# 23D_ESC_Controller.net
KiCad netlist of a schematic drawn in Altium Designer
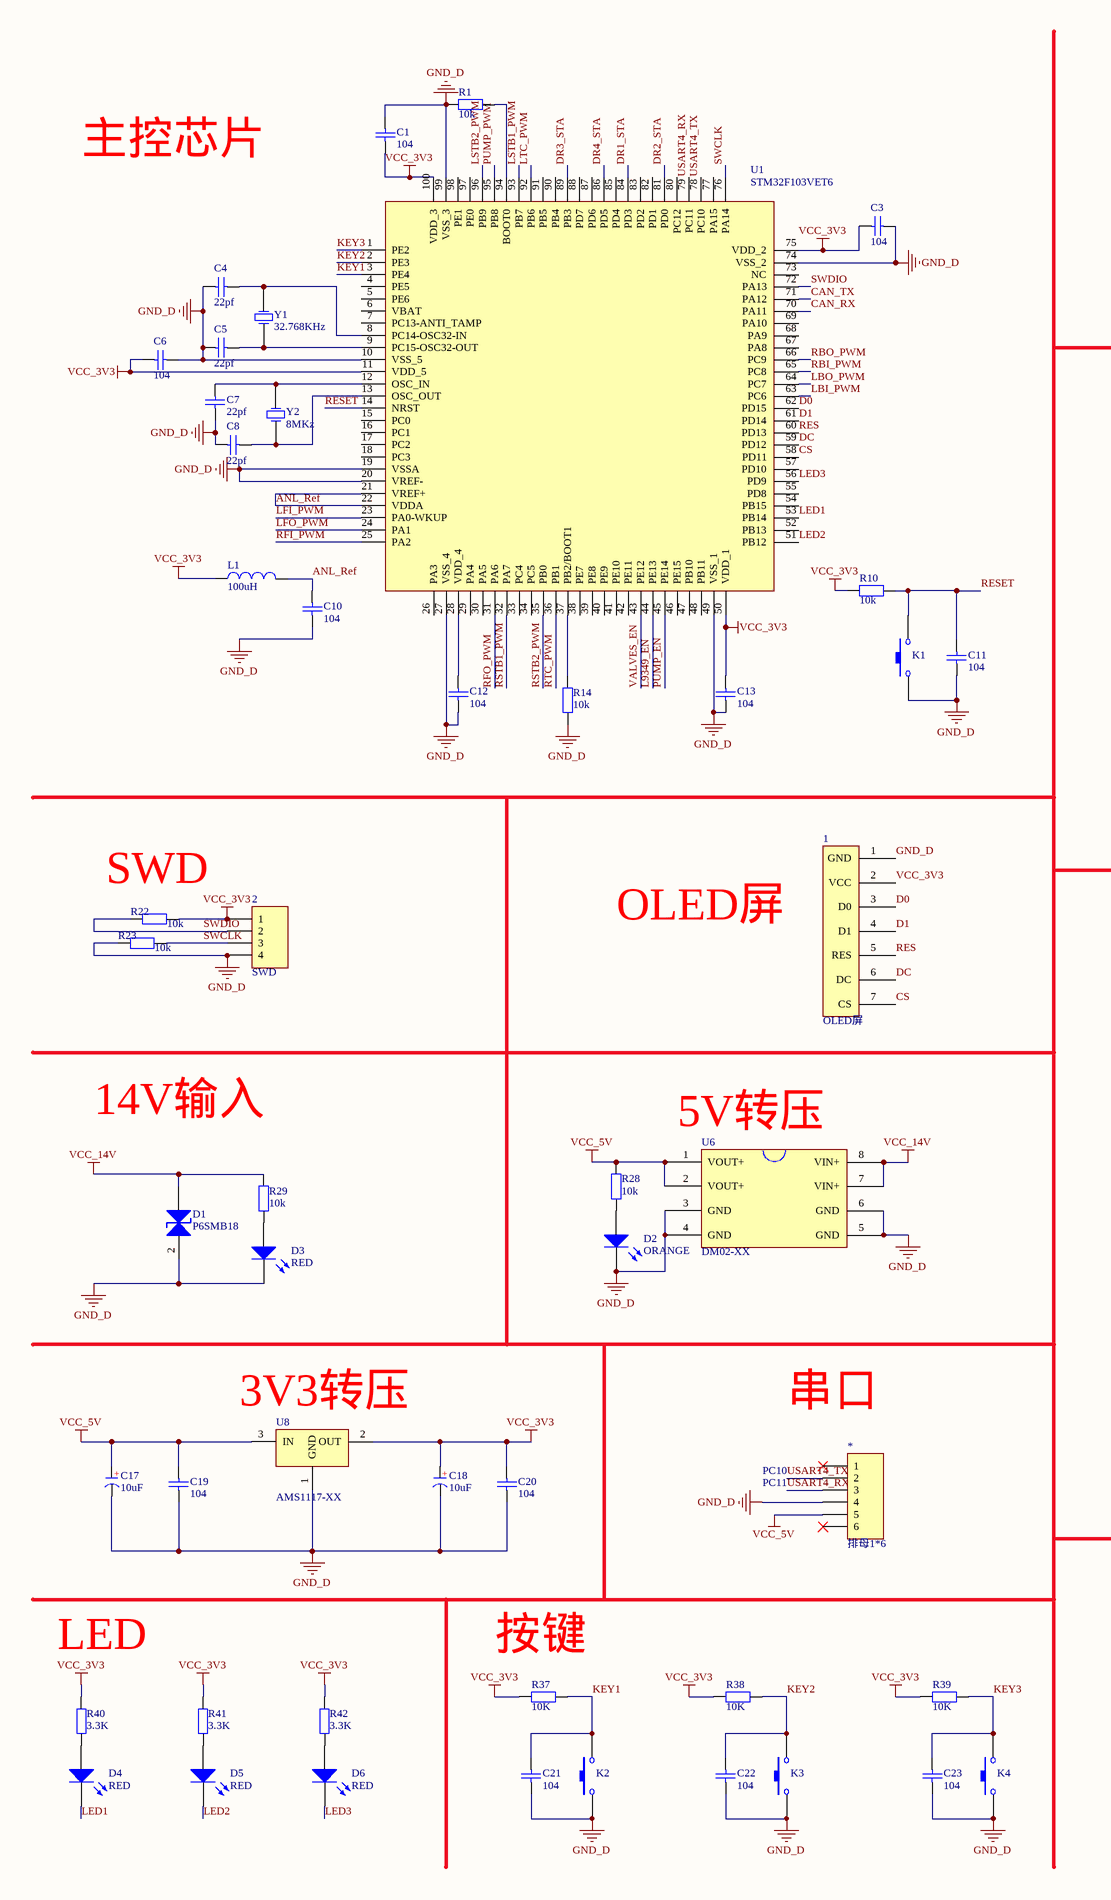
[diagram p0: 23D_ESC_Controller.SchDoc, left]
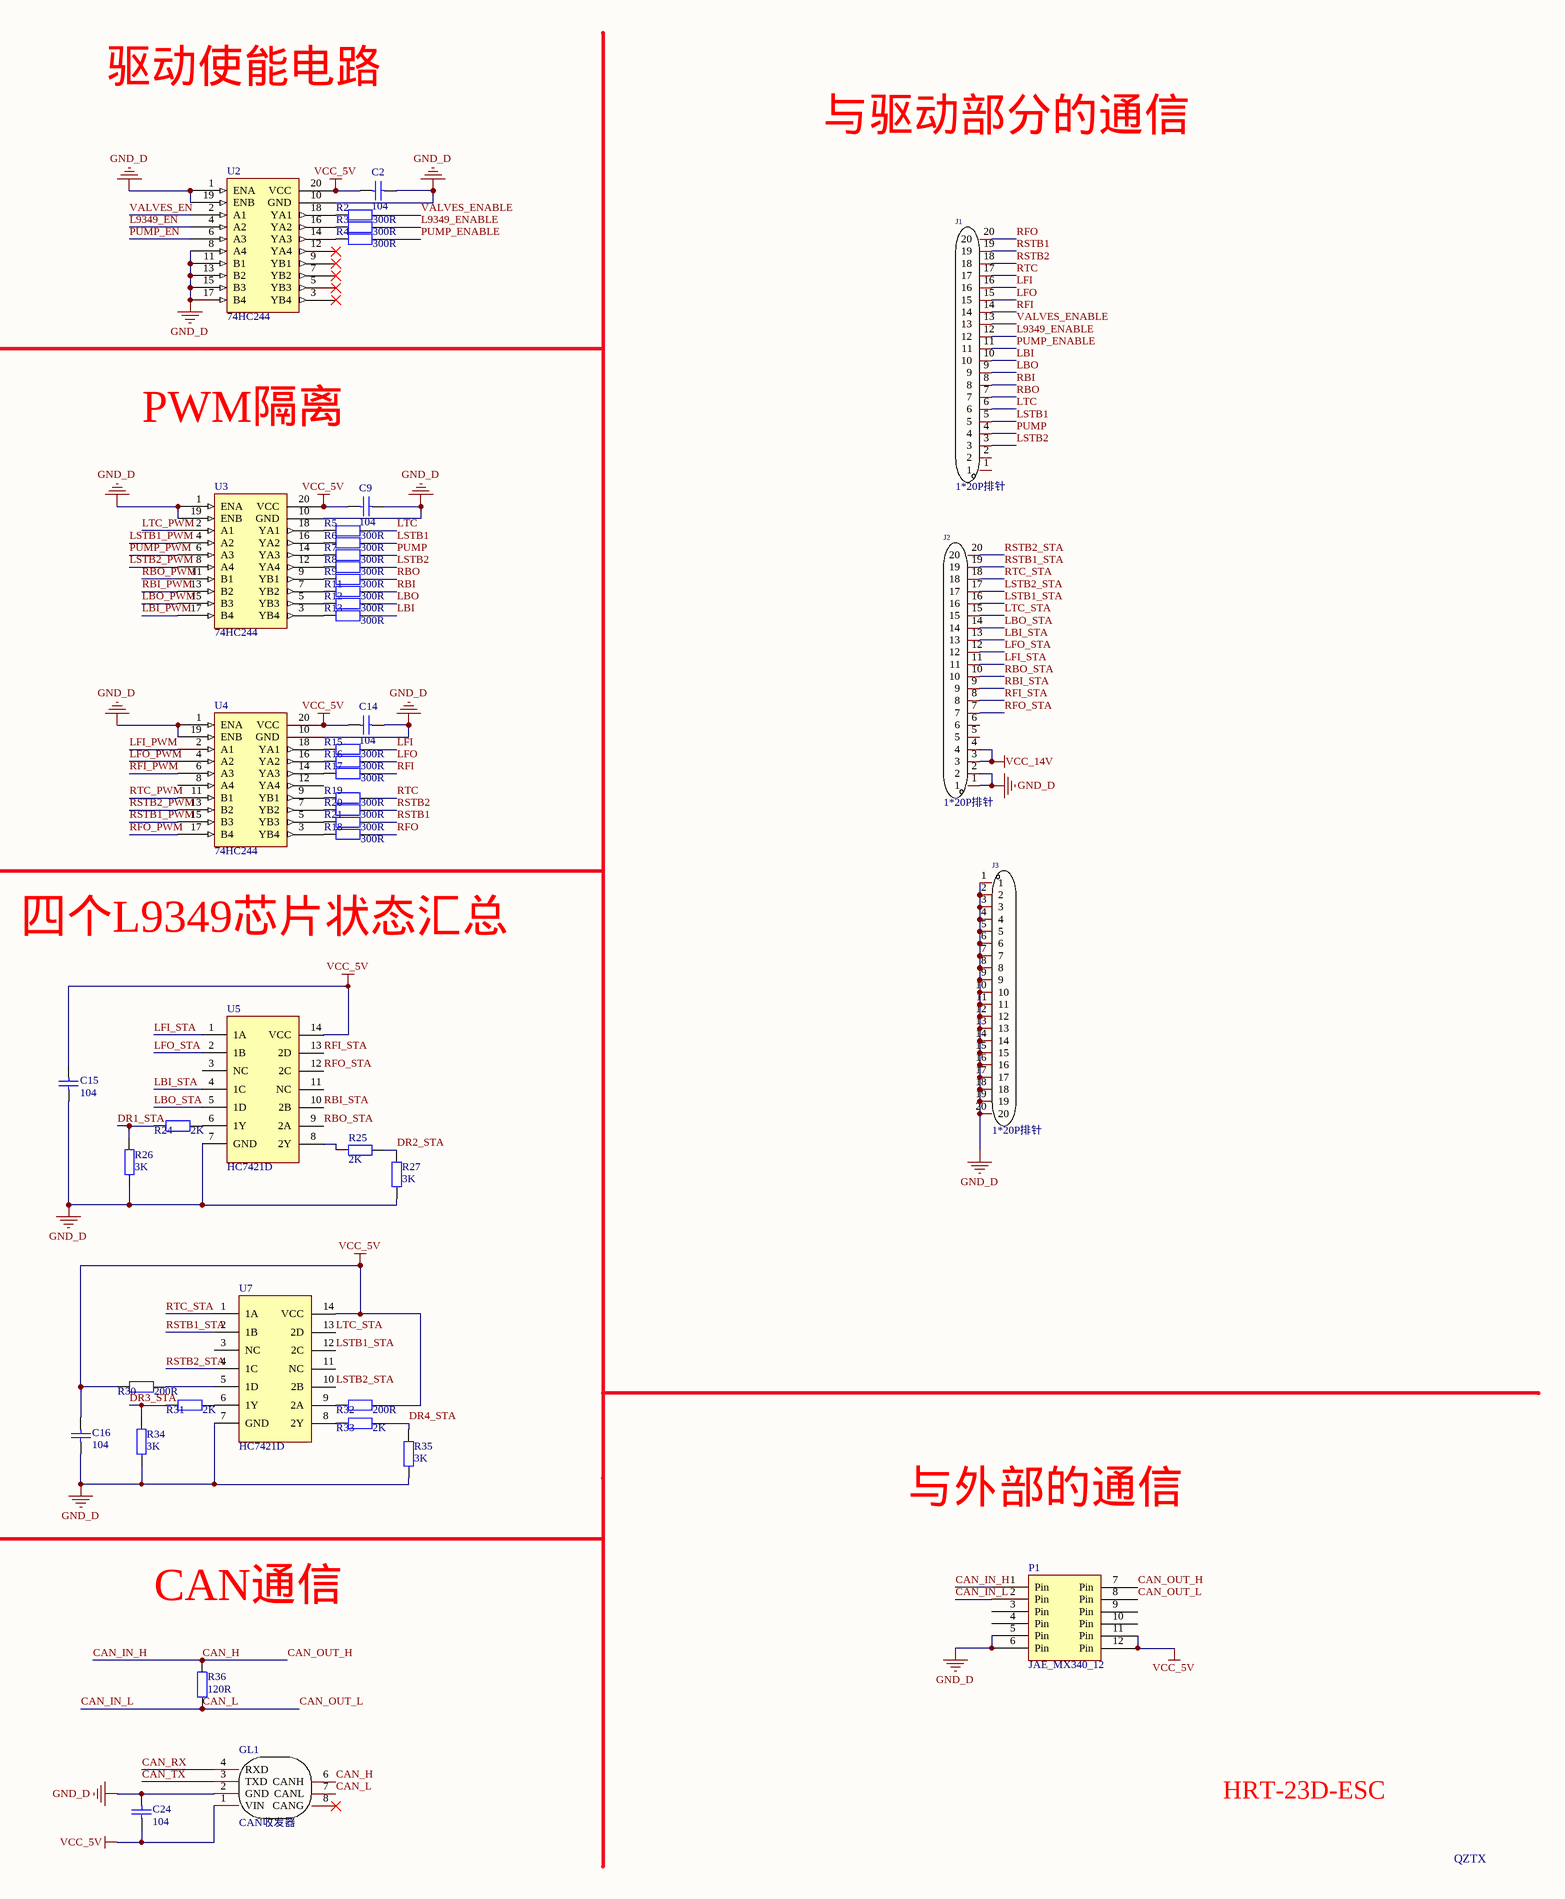
[diagram p1: 23D_ESC_Controller.SchDoc, right]

(export (version "E")
  (design (tool "Eeschema 10.0.6"))
  (components
    (comp (ref "*") (value "排母1*6") (footprint "HDR2.54-M-LI-6P") (libsource (lib "排针排母库") (part "排母1*6")))
    (comp (ref "1") (value "OLED屏") (footprint "HDR2.54-M-LI-7P") (libsource (lib "手柄按钮") (part "OLED屏")))
    (comp (ref "2") (value "SWD") (footprint "HDR2.54-LI-4P") (libsource (lib "排针排母库") (part "排针1*4")))
    (comp (ref "C1")
      (value "104")
      (footprint "C 0805")
      (description "无极性电容")
      (libsource (lib "HRT_D Schlib") (part "Cap"))
    )
    (comp (ref "C2")
      (value "104")
      (footprint "C 0805")
      (description "无极性电容")
      (libsource (lib "HRT_D Schlib") (part "Cap"))
    )
    (comp (ref "C3")
      (value "104")
      (footprint "C 0805")
      (description "无极性电容")
      (libsource (lib "HRT_D Schlib") (part "Cap"))
    )
    (comp (ref "C4")
      (value "22pf")
      (footprint "C 0805")
      (description "无极性电容")
      (libsource (lib "HRT_D Schlib") (part "Cap"))
    )
    (comp (ref "C5")
      (value "22pf")
      (footprint "C 0805")
      (description "无极性电容")
      (libsource (lib "HRT_D Schlib") (part "Cap"))
    )
    (comp (ref "C6")
      (value "104")
      (footprint "C 0805")
      (description "无极性电容")
      (libsource (lib "HRT_D Schlib") (part "Cap"))
    )
    (comp (ref "C7")
      (value "22pf")
      (footprint "C 0805")
      (description "无极性电容")
      (libsource (lib "HRT_D Schlib") (part "Cap"))
    )
    (comp (ref "C8")
      (value "22pf")
      (footprint "C 0805")
      (description "无极性电容")
      (libsource (lib "HRT_D Schlib") (part "Cap"))
    )
    (comp (ref "C9")
      (value "104")
      (footprint "C 0805")
      (description "无极性电容")
      (libsource (lib "HRT_D Schlib") (part "Cap"))
    )
    (comp (ref "C10")
      (value "104")
      (footprint "C 0805")
      (description "无极性电容")
      (libsource (lib "HRT_D Schlib") (part "Cap"))
    )
    (comp (ref "C11")
      (value "104")
      (footprint "C 0805")
      (description "无极性电容")
      (libsource (lib "HRT_D Schlib") (part "Cap"))
    )
    (comp (ref "C12")
      (value "104")
      (footprint "C 0805")
      (description "无极性电容")
      (libsource (lib "HRT_D Schlib") (part "Cap"))
    )
    (comp (ref "C13")
      (value "104")
      (footprint "C 0805")
      (description "无极性电容")
      (libsource (lib "HRT_D Schlib") (part "Cap"))
    )
    (comp (ref "C14")
      (value "104")
      (footprint "C 0805")
      (description "无极性电容")
      (libsource (lib "HRT_D Schlib") (part "Cap"))
    )
    (comp (ref "C15")
      (value "104")
      (footprint "C 0805")
      (description "无极性电容")
      (libsource (lib "HRT_D Schlib") (part "Cap"))
    )
    (comp (ref "C16")
      (value "104")
      (footprint "C 0805")
      (description "无极性电容")
      (libsource (lib "HRT_D Schlib") (part "Cap"))
    )
    (comp (ref "C17")
      (value "10uF")
      (footprint "CD B(3528)")
      (libsource (lib "USB_Gamepad_board") (part "贴片钽电容"))
    )
    (comp (ref "C18")
      (value "10uF")
      (footprint "CD B(3528)")
      (libsource (lib "USB_Gamepad_board") (part "贴片钽电容"))
    )
    (comp (ref "C19")
      (value "104")
      (footprint "C 0805")
      (description "无极性电容")
      (libsource (lib "HRT_D Schlib") (part "Cap"))
    )
    (comp (ref "C20")
      (value "104")
      (footprint "C 0805")
      (description "无极性电容")
      (libsource (lib "HRT_D Schlib") (part "Cap"))
    )
    (comp (ref "C21")
      (value "104")
      (footprint "C 0805")
      (description "无极性电容")
      (libsource (lib "HRT_D Schlib") (part "Cap"))
    )
    (comp (ref "C22")
      (value "104")
      (footprint "C 0805")
      (description "无极性电容")
      (libsource (lib "HRT_D Schlib") (part "Cap"))
    )
    (comp (ref "C23")
      (value "104")
      (footprint "C 0805")
      (description "无极性电容")
      (libsource (lib "HRT_D Schlib") (part "Cap"))
    )
    (comp (ref "C24")
      (value "104")
      (footprint "C 0805")
      (description "无极性电容")
      (libsource (lib "HRT_D Schlib") (part "Cap"))
    )
    (comp (ref "D1")
      (value "P6SMB18")
      (footprint "DO-214AA")
      (description "BiDir TVS Diode")
      (libsource (lib "ER100_ESC") (part "P6SMBXX"))
    )
    (comp (ref "D2")
      (value "ORANGE")
      (footprint "LED_0805")
      (description "发光二极管")
      (libsource (lib "ESC_control") (part "LED"))
    )
    (comp (ref "D3")
      (value "RED")
      (footprint "LED_0805")
      (description "发光二极管")
      (libsource (lib "ESC_control") (part "LED"))
    )
    (comp (ref "D4")
      (value "RED")
      (footprint "LED_0805")
      (description "发光二极管")
      (libsource (lib "ESC_control") (part "LED"))
    )
    (comp (ref "D5")
      (value "RED")
      (footprint "LED_0805")
      (description "发光二极管")
      (libsource (lib "ESC_control") (part "LED"))
    )
    (comp (ref "D6")
      (value "RED")
      (footprint "LED_0805")
      (description "发光二极管")
      (libsource (lib "ESC_control") (part "LED"))
    )
    (comp (ref "GL1")
      (value "CTM1051KT")
      (footprint "COMM-TH_7P-L19.9-W17.5-P2.54")
      (description "兼容3.3V和5V的单片机CAN接口，CAN隔离收发器 5V供电")
      (fields (field (name "MANUFACTURER") "ZLG(致远电子)") (field (name "NAME") "CAN收发器"))
      (libsource (lib "CTM1051KT大方块") (part "CTM1051KT_C84516"))
    )
    (comp (ref "J1")
      (value "2.54-1*20P直针")
      (footprint "HDR-TH_20P-P2.54-V-M-1")
      (fields (field (name "MANUFACTURER") "BOOMELE(博穆精密)") (field (name "NAME") "1*20P排针"))
      (libsource (lib "20P排针2.54mm") (part "2.54-1*20P直针"))
    )
    (comp (ref "J2")
      (value "2.54-1*20P直针")
      (footprint "HDR-TH_20P-P2.54-V-M-1")
      (fields (field (name "MANUFACTURER") "BOOMELE(博穆精密)") (field (name "NAME") "1*20P排针"))
      (libsource (lib "20P排针2.54mm") (part "2.54-1*20P直针"))
    )
    (comp (ref "J3")
      (value "2.54-1*20P直针")
      (footprint "HDR2.54-LI-20P")
      (fields (field (name "MANUFACTURER") "BOOMELE(博穆精密)") (field (name "NAME") "1*20P排针"))
      (libsource (lib "20P排针2.54mm") (part "2.54-1*20P直针"))
    )
    (comp (ref "K1")
      (value "Key")
      (footprint "KEY 3.6*2.5 SMD")
      (description "按键")
      (libsource (lib "HRT_D Schlib") (part "Key"))
    )
    (comp (ref "K2")
      (value "Key")
      (footprint "KEY 3.6*2.5 SMD")
      (description "按键")
      (libsource (lib "HRT_D Schlib") (part "Key"))
    )
    (comp (ref "K3")
      (value "Key")
      (footprint "KEY 3.6*2.5 SMD")
      (description "按键")
      (libsource (lib "HRT_D Schlib") (part "Key"))
    )
    (comp (ref "K4")
      (value "Key")
      (footprint "KEY 3.6*2.5 SMD")
      (description "按键")
      (libsource (lib "HRT_D Schlib") (part "Key"))
    )
    (comp (ref "L1")
      (value "100uH")
      (footprint "L 0805")
      (description "电感")
      (libsource (lib "ESC_control") (part "Inductor"))
    )
    (comp (ref "P1")
      (value "JAE_MX340_12")
      (footprint "JAE_MX34_2.2_12")
      (libsource (lib "ESC_control") (part "JAE_MX34012NF1"))
    )
    (comp (ref "R1")
      (value "10k")
      (footprint "R 0805")
      (description "电阻")
      (libsource (lib "ESC_control") (part "Resistor"))
    )
    (comp (ref "R2")
      (value "300R")
      (footprint "R 0805")
      (description "电阻")
      (libsource (lib "") (part "Resistor_1"))
    )
    (comp (ref "R3")
      (value "300R")
      (footprint "R 0805")
      (description "电阻")
      (libsource (lib "") (part "Resistor_1"))
    )
    (comp (ref "R4")
      (value "300R")
      (footprint "R 0805")
      (description "电阻")
      (libsource (lib "") (part "Resistor_1"))
    )
    (comp (ref "R5")
      (value "300R")
      (footprint "R 0805")
      (description "电阻")
      (libsource (lib "") (part "Resistor_1"))
    )
    (comp (ref "R6")
      (value "300R")
      (footprint "R 0805")
      (description "电阻")
      (libsource (lib "") (part "Resistor_1"))
    )
    (comp (ref "R7")
      (value "300R")
      (footprint "R 0805")
      (description "电阻")
      (libsource (lib "") (part "Resistor_1"))
    )
    (comp (ref "R8")
      (value "300R")
      (footprint "R 0805")
      (description "电阻")
      (libsource (lib "") (part "Resistor_1"))
    )
    (comp (ref "R9")
      (value "300R")
      (footprint "R 0805")
      (description "电阻")
      (libsource (lib "") (part "Resistor_1"))
    )
    (comp (ref "R10")
      (value "10k")
      (footprint "R 0805")
      (description "电阻")
      (libsource (lib "") (part "Resistor_1"))
    )
    (comp (ref "R11")
      (value "300R")
      (footprint "R 0805")
      (description "电阻")
      (libsource (lib "") (part "Resistor_1"))
    )
    (comp (ref "R12")
      (value "300R")
      (footprint "R 0805")
      (description "电阻")
      (libsource (lib "") (part "Resistor_1"))
    )
    (comp (ref "R13")
      (value "300R")
      (footprint "R 0805")
      (description "电阻")
      (libsource (lib "") (part "Resistor_1"))
    )
    (comp (ref "R14")
      (value "10k")
      (footprint "R 0805")
      (description "电阻")
      (libsource (lib "") (part "Resistor_3"))
    )
    (comp (ref "R15")
      (value "300R")
      (footprint "R 0805")
      (description "电阻")
      (libsource (lib "") (part "Resistor_1"))
    )
    (comp (ref "R16")
      (value "300R")
      (footprint "R 0805")
      (description "电阻")
      (libsource (lib "") (part "Resistor_1"))
    )
    (comp (ref "R17")
      (value "300R")
      (footprint "R 0805")
      (description "电阻")
      (libsource (lib "") (part "Resistor_1"))
    )
    (comp (ref "R18")
      (value "300R")
      (footprint "R 0805")
      (description "电阻")
      (libsource (lib "") (part "Resistor_1"))
    )
    (comp (ref "R19")
      (value "300R")
      (footprint "R 0805")
      (description "电阻")
      (libsource (lib "") (part "Resistor_1"))
    )
    (comp (ref "R20")
      (value "300R")
      (footprint "R 0805")
      (description "电阻")
      (libsource (lib "") (part "Resistor_1"))
    )
    (comp (ref "R21")
      (value "300R")
      (footprint "R 0805")
      (description "电阻")
      (libsource (lib "") (part "Resistor_1"))
    )
    (comp (ref "R22")
      (value "10k")
      (footprint "R 0805")
      (description "电阻")
      (libsource (lib "") (part "Resistor_1"))
    )
    (comp (ref "R23")
      (value "10k")
      (footprint "R 0805")
      (description "电阻")
      (libsource (lib "") (part "Resistor_1"))
    )
    (comp (ref "R24")
      (value "2K")
      (footprint "R 0805")
      (description "电阻")
      (libsource (lib "ESC_control") (part "Resistor"))
    )
    (comp (ref "R25")
      (value "2K")
      (footprint "R 0805")
      (description "电阻")
      (libsource (lib "") (part "Resistor_1"))
    )
    (comp (ref "R26")
      (value "3K")
      (footprint "R 0805")
      (description "电阻")
      (libsource (lib "") (part "Resistor_2"))
    )
    (comp (ref "R27")
      (value "3K")
      (footprint "R 0805")
      (description "电阻")
      (libsource (lib "") (part "Resistor_3"))
    )
    (comp (ref "R28")
      (value "10k")
      (footprint "R 0805")
      (description "电阻")
      (libsource (lib "") (part "Resistor_2"))
    )
    (comp (ref "R29")
      (value "10k")
      (footprint "R 0805")
      (description "电阻")
      (libsource (lib "") (part "Resistor_2"))
    )
    (comp (ref "R30")
      (value "200R")
      (footprint "R 0805")
      (description "电阻")
      (libsource (lib "ESC_control") (part "Resistor"))
    )
    (comp (ref "R31")
      (value "2K")
      (footprint "R 0805")
      (description "电阻")
      (libsource (lib "ESC_control") (part "Resistor"))
    )
    (comp (ref "R32")
      (value "200R")
      (footprint "R 0805")
      (description "电阻")
      (libsource (lib "ESC_control") (part "Resistor"))
    )
    (comp (ref "R33")
      (value "2K")
      (footprint "R 0805")
      (description "电阻")
      (libsource (lib "ESC_control") (part "Resistor"))
    )
    (comp (ref "R34")
      (value "3K")
      (footprint "R 0805")
      (description "电阻")
      (libsource (lib "") (part "Resistor_2"))
    )
    (comp (ref "R35")
      (value "3K")
      (footprint "R 0805")
      (description "电阻")
      (libsource (lib "") (part "Resistor_3"))
    )
    (comp (ref "R36")
      (value "120R")
      (footprint "R 0805")
      (description "电阻")
      (libsource (lib "") (part "Resistor_3"))
    )
    (comp (ref "R37")
      (value "10K")
      (footprint "R 0805")
      (description "电阻")
      (libsource (lib "ESC_control") (part "Resistor"))
    )
    (comp (ref "R38")
      (value "10K")
      (footprint "R 0805")
      (description "电阻")
      (libsource (lib "ESC_control") (part "Resistor"))
    )
    (comp (ref "R39")
      (value "10K")
      (footprint "R 0805")
      (description "电阻")
      (libsource (lib "ESC_control") (part "Resistor"))
    )
    (comp (ref "R40")
      (value "3.3K")
      (footprint "R 0805")
      (description "电阻")
      (libsource (lib "") (part "Resistor_2"))
    )
    (comp (ref "R41")
      (value "3.3K")
      (footprint "R 0805")
      (description "电阻")
      (libsource (lib "") (part "Resistor_2"))
    )
    (comp (ref "R42")
      (value "3.3K")
      (footprint "R 0805")
      (description "电阻")
      (libsource (lib "") (part "Resistor_2"))
    )
    (comp (ref "U1")
      (value "STM32F103VET6")
      (footprint "TQFP100N50P14X14X1.2")
      (libsource (lib "STM32") (part "STM32F103RBT6"))
    )
    (comp (ref "U2")
      (value "74HC244")
      (footprint "SSOP20")
      (description "CMOS工艺8通道缓冲器")
      (libsource (lib "ESC_control") (part "74HC244"))
    )
    (comp (ref "U3")
      (value "74HC244")
      (footprint "SSOP20")
      (description "CMOS工艺8通道缓冲器")
      (libsource (lib "ESC_control") (part "74HC244"))
    )
    (comp (ref "U4")
      (value "74HC244")
      (footprint "SSOP20")
      (description "CMOS工艺8通道缓冲器")
      (libsource (lib "ESC_control") (part "74HC244"))
    )
    (comp (ref "U5") (value "HC7421D") (footprint "74hc74") (libsource (lib "ESC_control") (part "HC7421D")))
    (comp (ref "U6")
      (value "DM02-XX")
      (footprint "DM02")
      (description "开关型DC-DC变换器")
      (libsource (lib "ESC_control") (part "DM02"))
    )
    (comp (ref "U7") (value "HC7421D") (footprint "74hc74") (libsource (lib "ESC_control") (part "HC7421D")))
    (comp (ref "U8")
      (value "AMS1117-XX")
      (footprint "SOT223")
      (description "线性稳压器")
      (libsource (lib "HRT_D Schlib") (part "AMS1117"))
    )
    (comp (ref "Y1")
      (value "32.768KHz")
      (footprint "XTAL-5032")
      (description "晶振")
      (libsource (lib "ESC_control") (part "XTAL"))
    )
    (comp (ref "Y2")
      (value "8MKz")
      (footprint "XTAL-5032")
      (description "晶振")
      (libsource (lib "ESC_control") (part "XTAL"))
    )
  )
  (nets
    (net (code "1") (name "/ANL_Ref") (class "Default")
      (node (ref "C10") (pin "1") (pinfunction "1_1") (pintype "passive"))
      (node (ref "L1") (pin "2") (pinfunction "2_2") (pintype "passive"))
      (node (ref "U1") (pin "21") (pinfunction "VREF+_21") (pintype "passive"))
      (node (ref "U1") (pin "22") (pinfunction "VDDA_22") (pintype "passive"))
    )
    (net (code "2") (name "/CAN_H") (class "Default")
      (node (ref "GL1") (pin "6") (pinfunction "CANH_6") (pintype "passive"))
      (node (ref "P1") (pin "1") (pinfunction "Pin_1") (pintype "passive"))
      (node (ref "P1") (pin "7") (pinfunction "Pin_7") (pintype "passive"))
      (node (ref "R36") (pin "1") (pinfunction "1_1") (pintype "passive"))
    )
    (net (code "3") (name "/CAN_IN_L") (class "Default")
      (node (ref "GL1") (pin "7") (pinfunction "CANL_7") (pintype "passive"))
      (node (ref "P1") (pin "2") (pinfunction "Pin_2") (pintype "passive"))
      (node (ref "P1") (pin "8") (pinfunction "Pin_8") (pintype "passive"))
      (node (ref "R36") (pin "2") (pinfunction "2_2") (pintype "passive"))
    )
    (net (code "4") (name "/CAN_RX") (class "Default")
      (node (ref "GL1") (pin "4") (pinfunction "RXD_4") (pintype "passive"))
      (node (ref "U1") (pin "70") (pinfunction "PA11_70") (pintype "passive"))
    )
    (net (code "5") (name "/CAN_TX") (class "Default")
      (node (ref "GL1") (pin "3") (pinfunction "TXD_3") (pintype "passive"))
      (node (ref "U1") (pin "71") (pinfunction "PA12_71") (pintype "passive"))
    )
    (net (code "6") (name "/CS") (class "Default")
      (node (ref "1") (pin "7") (pinfunction "CS_7") (pintype "passive"))
      (node (ref "U1") (pin "58") (pinfunction "PD11_58") (pintype "passive"))
    )
    (net (code "7") (name "/D0") (class "Default")
      (node (ref "1") (pin "3") (pinfunction "D0_3") (pintype "passive"))
      (node (ref "U1") (pin "62") (pinfunction "PD15_62") (pintype "passive"))
    )
    (net (code "8") (name "/D1") (class "Default")
      (node (ref "1") (pin "4") (pinfunction "D1_4") (pintype "passive"))
      (node (ref "U1") (pin "61") (pinfunction "PD14_61") (pintype "passive"))
    )
    (net (code "9") (name "/DC") (class "Default")
      (node (ref "1") (pin "6") (pinfunction "DC_6") (pintype "passive"))
      (node (ref "U1") (pin "59") (pinfunction "PD12_59") (pintype "passive"))
    )
    (net (code "10") (name "/DR1_STA") (class "Default")
      (node (ref "R24") (pin "2") (pinfunction "2_2") (pintype "passive"))
      (node (ref "R26") (pin "2") (pinfunction "2_2") (pintype "passive"))
      (node (ref "U1") (pin "84") (pinfunction "PD3_84") (pintype "passive"))
    )
    (net (code "11") (name "/DR2_STA") (class "Default")
      (node (ref "R25") (pin "2") (pinfunction "2_2") (pintype "passive"))
      (node (ref "R27") (pin "1") (pinfunction "1_1") (pintype "passive"))
      (node (ref "U1") (pin "81") (pinfunction "PD0_81") (pintype "passive"))
    )
    (net (code "12") (name "/DR3_STA") (class "Default")
      (node (ref "R31") (pin "2") (pinfunction "2_2") (pintype "passive"))
      (node (ref "R34") (pin "2") (pinfunction "2_2") (pintype "passive"))
      (node (ref "U1") (pin "89") (pinfunction "PB3_89") (pintype "passive"))
    )
    (net (code "13") (name "/DR4_STA") (class "Default")
      (node (ref "R33") (pin "1") (pinfunction "1_1") (pintype "passive"))
      (node (ref "R35") (pin "1") (pinfunction "1_1") (pintype "passive"))
      (node (ref "U1") (pin "86") (pinfunction "PD5_86") (pintype "passive"))
    )
    (net (code "14") (name "/KEY1") (class "Default")
      (node (ref "C21") (pin "1") (pinfunction "1_1") (pintype "passive"))
      (node (ref "K2") (pin "2") (pinfunction "2_2") (pintype "passive"))
      (node (ref "R37") (pin "1") (pinfunction "1_1") (pintype "passive"))
      (node (ref "U1") (pin "3") (pinfunction "PE4_3") (pintype "passive"))
    )
    (net (code "15") (name "/KEY2") (class "Default")
      (node (ref "C22") (pin "1") (pinfunction "1_1") (pintype "passive"))
      (node (ref "K3") (pin "2") (pinfunction "2_2") (pintype "passive"))
      (node (ref "R38") (pin "1") (pinfunction "1_1") (pintype "passive"))
      (node (ref "U1") (pin "2") (pinfunction "PE3_2") (pintype "passive"))
    )
    (net (code "16") (name "/KEY3") (class "Default")
      (node (ref "C23") (pin "1") (pinfunction "1_1") (pintype "passive"))
      (node (ref "K4") (pin "2") (pinfunction "2_2") (pintype "passive"))
      (node (ref "R39") (pin "1") (pinfunction "1_1") (pintype "passive"))
      (node (ref "U1") (pin "1") (pinfunction "PE2_1") (pintype "passive"))
    )
    (net (code "17") (name "/L9349_EN") (class "Default")
      (node (ref "U1") (pin "44") (pinfunction "PE13_44") (pintype "passive"))
      (node (ref "U2") (pin "4") (pinfunction "A2_4") (pintype "input"))
    )
    (net (code "18") (name "/L9349_ENABLE") (class "Default")
      (node (ref "J1") (pin "12") (pinfunction "12_12") (pintype "passive"))
      (node (ref "R3") (pin "2") (pinfunction "2_2") (pintype "passive"))
    )
    (net (code "19") (name "/LBI") (class "Default")
      (node (ref "J1") (pin "10") (pinfunction "10_10") (pintype "passive"))
      (node (ref "R13") (pin "2") (pinfunction "2_2") (pintype "passive"))
    )
    (net (code "20") (name "/LBI_PWM") (class "Default")
      (node (ref "U1") (pin "63") (pinfunction "PC6_63") (pintype "passive"))
      (node (ref "U3") (pin "17") (pinfunction "B4_17") (pintype "input"))
    )
    (net (code "21") (name "/LBI_STA") (class "Default")
      (node (ref "J2") (pin "13") (pinfunction "13_13") (pintype "passive"))
      (node (ref "U5") (pin "4") (pinfunction "1C_4") (pintype "passive"))
    )
    (net (code "22") (name "/LBO") (class "Default")
      (node (ref "J1") (pin "9") (pinfunction "9_9") (pintype "passive"))
      (node (ref "R12") (pin "2") (pinfunction "2_2") (pintype "passive"))
    )
    (net (code "23") (name "/LBO_PWM") (class "Default")
      (node (ref "U1") (pin "64") (pinfunction "PC7_64") (pintype "passive"))
      (node (ref "U3") (pin "15") (pinfunction "B3_15") (pintype "input"))
    )
    (net (code "24") (name "/LBO_STA") (class "Default")
      (node (ref "J2") (pin "14") (pinfunction "14_14") (pintype "passive"))
      (node (ref "U5") (pin "5") (pinfunction "1D_5") (pintype "passive"))
    )
    (net (code "25") (name "/LED1") (class "Default")
      (node (ref "D4") (pin "2") (pinfunction "K_2") (pintype "passive"))
      (node (ref "U1") (pin "53") (pinfunction "PB14_53") (pintype "passive"))
    )
    (net (code "26") (name "/LED2") (class "Default")
      (node (ref "D5") (pin "2") (pinfunction "K_2") (pintype "passive"))
      (node (ref "U1") (pin "51") (pinfunction "PB12_51") (pintype "passive"))
    )
    (net (code "27") (name "/LED3") (class "Default")
      (node (ref "D6") (pin "2") (pinfunction "K_2") (pintype "passive"))
      (node (ref "U1") (pin "56") (pinfunction "PD9_56") (pintype "passive"))
    )
    (net (code "28") (name "/LFI") (class "Default")
      (node (ref "J1") (pin "16") (pinfunction "16_16") (pintype "passive"))
      (node (ref "R15") (pin "2") (pinfunction "2_2") (pintype "passive"))
    )
    (net (code "29") (name "/LFI_PWM") (class "Default")
      (node (ref "U1") (pin "23") (pinfunction "PA0-WKUP_23") (pintype "passive"))
      (node (ref "U4") (pin "2") (pinfunction "A1_2") (pintype "input"))
    )
    (net (code "30") (name "/LFI_STA") (class "Default")
      (node (ref "J2") (pin "11") (pinfunction "11_11") (pintype "passive"))
      (node (ref "U5") (pin "1") (pinfunction "1A_1") (pintype "passive"))
    )
    (net (code "31") (name "/LFO") (class "Default")
      (node (ref "J1") (pin "15") (pinfunction "15_15") (pintype "passive"))
      (node (ref "R16") (pin "2") (pinfunction "2_2") (pintype "passive"))
    )
    (net (code "32") (name "/LFO_PWM") (class "Default")
      (node (ref "U1") (pin "24") (pinfunction "PA1_24") (pintype "passive"))
      (node (ref "U4") (pin "4") (pinfunction "A2_4") (pintype "input"))
    )
    (net (code "33") (name "/LFO_STA") (class "Default")
      (node (ref "J2") (pin "12") (pinfunction "12_12") (pintype "passive"))
      (node (ref "U5") (pin "2") (pinfunction "1B_2") (pintype "passive"))
    )
    (net (code "34") (name "/LSTB1") (class "Default")
      (node (ref "J1") (pin "5") (pinfunction "5_5") (pintype "passive"))
      (node (ref "R6") (pin "2") (pinfunction "2_2") (pintype "passive"))
    )
    (net (code "35") (name "/LSTB1_PWM") (class "Default")
      (node (ref "U1") (pin "93") (pinfunction "PB7_93") (pintype "passive"))
      (node (ref "U3") (pin "4") (pinfunction "A2_4") (pintype "input"))
    )
    (net (code "36") (name "/LSTB1_STA") (class "Default")
      (node (ref "J2") (pin "16") (pinfunction "16_16") (pintype "passive"))
      (node (ref "U7") (pin "12") (pinfunction "2C_12") (pintype "passive"))
    )
    (net (code "37") (name "/LSTB2") (class "Default")
      (node (ref "J1") (pin "3") (pinfunction "3_3") (pintype "passive"))
      (node (ref "R8") (pin "2") (pinfunction "2_2") (pintype "passive"))
    )
    (net (code "38") (name "/LSTB2_PWM") (class "Default")
      (node (ref "U1") (pin "96") (pinfunction "PB9_96") (pintype "passive"))
      (node (ref "U3") (pin "8") (pinfunction "A4_8") (pintype "input"))
    )
    (net (code "39") (name "/LSTB2_STA") (class "Default")
      (node (ref "J2") (pin "17") (pinfunction "17_17") (pintype "passive"))
      (node (ref "U7") (pin "10") (pinfunction "2B_10") (pintype "passive"))
    )
    (net (code "40") (name "/LTC") (class "Default")
      (node (ref "J1") (pin "6") (pinfunction "6_6") (pintype "passive"))
      (node (ref "R5") (pin "2") (pinfunction "2_2") (pintype "passive"))
    )
    (net (code "41") (name "/LTC_PWM") (class "Default")
      (node (ref "U1") (pin "92") (pinfunction "PB6_92") (pintype "passive"))
      (node (ref "U3") (pin "2") (pinfunction "A1_2") (pintype "input"))
    )
    (net (code "42") (name "/LTC_STA") (class "Default")
      (node (ref "J2") (pin "15") (pinfunction "15_15") (pintype "passive"))
      (node (ref "U7") (pin "13") (pinfunction "2D_13") (pintype "passive"))
    )
    (net (code "43") (name "/PUMP") (class "Default")
      (node (ref "J1") (pin "4") (pinfunction "4_4") (pintype "passive"))
      (node (ref "R7") (pin "2") (pinfunction "2_2") (pintype "passive"))
    )
    (net (code "44") (name "/PUMP_EN") (class "Default")
      (node (ref "U1") (pin "45") (pinfunction "PE14_45") (pintype "passive"))
      (node (ref "U2") (pin "6") (pinfunction "A3_6") (pintype "input"))
    )
    (net (code "45") (name "/PUMP_ENABLE") (class "Default")
      (node (ref "J1") (pin "11") (pinfunction "11_11") (pintype "passive"))
      (node (ref "R4") (pin "2") (pinfunction "2_2") (pintype "passive"))
    )
    (net (code "46") (name "/PUMP_PWM") (class "Default")
      (node (ref "U1") (pin "95") (pinfunction "PB8_95") (pintype "passive"))
      (node (ref "U3") (pin "6") (pinfunction "A3_6") (pintype "input"))
    )
    (net (code "47") (name "/RBI") (class "Default")
      (node (ref "J1") (pin "8") (pinfunction "8_8") (pintype "passive"))
      (node (ref "R11") (pin "2") (pinfunction "2_2") (pintype "passive"))
    )
    (net (code "48") (name "/RBI_PWM") (class "Default")
      (node (ref "U1") (pin "65") (pinfunction "PC8_65") (pintype "passive"))
      (node (ref "U3") (pin "13") (pinfunction "B2_13") (pintype "input"))
    )
    (net (code "49") (name "/RBI_STA") (class "Default")
      (node (ref "J2") (pin "9") (pinfunction "9_9") (pintype "passive"))
      (node (ref "U5") (pin "10") (pinfunction "2B_10") (pintype "passive"))
    )
    (net (code "50") (name "/RBO") (class "Default")
      (node (ref "J1") (pin "7") (pinfunction "7_7") (pintype "passive"))
      (node (ref "R9") (pin "2") (pinfunction "2_2") (pintype "passive"))
    )
    (net (code "51") (name "/RBO_PWM") (class "Default")
      (node (ref "U1") (pin "66") (pinfunction "PC9_66") (pintype "passive"))
      (node (ref "U3") (pin "11") (pinfunction "B1_11") (pintype "input"))
    )
    (net (code "52") (name "/RBO_STA") (class "Default")
      (node (ref "J2") (pin "10") (pinfunction "10_10") (pintype "passive"))
      (node (ref "U5") (pin "9") (pinfunction "2A_9") (pintype "passive"))
    )
    (net (code "53") (name "/RES") (class "Default")
      (node (ref "1") (pin "5") (pinfunction "RES_5") (pintype "passive"))
      (node (ref "U1") (pin "60") (pinfunction "PD13_60") (pintype "passive"))
    )
    (net (code "54") (name "/RESET") (class "Default")
      (node (ref "C11") (pin "1") (pinfunction "1_1") (pintype "passive"))
      (node (ref "K1") (pin "2") (pinfunction "2_2") (pintype "passive"))
      (node (ref "R10") (pin "2") (pinfunction "2_2") (pintype "passive"))
      (node (ref "U1") (pin "14") (pinfunction "NRST_14") (pintype "passive"))
    )
    (net (code "55") (name "/RFI") (class "Default")
      (node (ref "J1") (pin "14") (pinfunction "14_14") (pintype "passive"))
      (node (ref "R17") (pin "2") (pinfunction "2_2") (pintype "passive"))
    )
    (net (code "56") (name "/RFI_PWM") (class "Default")
      (node (ref "U1") (pin "25") (pinfunction "PA2_25") (pintype "passive"))
      (node (ref "U4") (pin "6") (pinfunction "A3_6") (pintype "input"))
    )
    (net (code "57") (name "/RFI_STA") (class "Default")
      (node (ref "J2") (pin "8") (pinfunction "8_8") (pintype "passive"))
      (node (ref "U5") (pin "13") (pinfunction "2D_13") (pintype "passive"))
    )
    (net (code "58") (name "/RFO") (class "Default")
      (node (ref "J1") (pin "20") (pinfunction "20_20") (pintype "passive"))
      (node (ref "R18") (pin "2") (pinfunction "2_2") (pintype "passive"))
    )
    (net (code "59") (name "/RFO_PWM") (class "Default")
      (node (ref "U1") (pin "31") (pinfunction "PA6_31") (pintype "passive"))
      (node (ref "U4") (pin "17") (pinfunction "B4_17") (pintype "input"))
    )
    (net (code "60") (name "/RFO_STA") (class "Default")
      (node (ref "J2") (pin "7") (pinfunction "7_7") (pintype "passive"))
      (node (ref "U5") (pin "12") (pinfunction "2C_12") (pintype "passive"))
    )
    (net (code "61") (name "/RSTB1") (class "Default")
      (node (ref "J1") (pin "19") (pinfunction "19_19") (pintype "passive"))
      (node (ref "R21") (pin "2") (pinfunction "2_2") (pintype "passive"))
    )
    (net (code "62") (name "/RSTB1_PWM") (class "Default")
      (node (ref "U1") (pin "32") (pinfunction "PA7_32") (pintype "passive"))
      (node (ref "U4") (pin "15") (pinfunction "B3_15") (pintype "input"))
    )
    (net (code "63") (name "/RSTB1_STA") (class "Default")
      (node (ref "J2") (pin "19") (pinfunction "19_19") (pintype "passive"))
      (node (ref "U7") (pin "2") (pinfunction "1B_2") (pintype "passive"))
    )
    (net (code "64") (name "/RSTB2") (class "Default")
      (node (ref "J1") (pin "18") (pinfunction "18_18") (pintype "passive"))
      (node (ref "R20") (pin "2") (pinfunction "2_2") (pintype "passive"))
    )
    (net (code "65") (name "/RSTB2_PWM") (class "Default")
      (node (ref "U1") (pin "35") (pinfunction "PB0_35") (pintype "passive"))
      (node (ref "U4") (pin "13") (pinfunction "B2_13") (pintype "input"))
    )
    (net (code "66") (name "/RSTB2_STA") (class "Default")
      (node (ref "J2") (pin "20") (pinfunction "20_20") (pintype "passive"))
      (node (ref "U7") (pin "4") (pinfunction "1C_4") (pintype "passive"))
    )
    (net (code "67") (name "/RTC") (class "Default")
      (node (ref "J1") (pin "17") (pinfunction "17_17") (pintype "passive"))
      (node (ref "R19") (pin "2") (pinfunction "2_2") (pintype "passive"))
    )
    (net (code "68") (name "/RTC_PWM") (class "Default")
      (node (ref "U1") (pin "36") (pinfunction "PB1_36") (pintype "passive"))
      (node (ref "U4") (pin "11") (pinfunction "B1_11") (pintype "input"))
    )
    (net (code "69") (name "/RTC_STA") (class "Default")
      (node (ref "J2") (pin "18") (pinfunction "18_18") (pintype "passive"))
      (node (ref "U7") (pin "1") (pinfunction "1A_1") (pintype "passive"))
    )
    (net (code "70") (name "/SWCLK") (class "Default")
      (node (ref "2") (pin "3") (pinfunction "3_3") (pintype "passive"))
      (node (ref "R23") (pin "2") (pinfunction "2_2") (pintype "passive"))
      (node (ref "U1") (pin "76") (pinfunction "PA14_76") (pintype "passive"))
    )
    (net (code "71") (name "/SWDIO") (class "Default")
      (node (ref "2") (pin "2") (pinfunction "2_2") (pintype "passive"))
      (node (ref "R22") (pin "1") (pinfunction "1_1") (pintype "passive"))
      (node (ref "U1") (pin "72") (pinfunction "PA13_72") (pintype "passive"))
    )
    (net (code "72") (name "/USART4_RX") (class "Default")
      (node (ref "*") (pin "3") (pinfunction "3_3") (pintype "passive"))
      (node (ref "U1") (pin "79") (pinfunction "PC11_79") (pintype "passive"))
    )
    (net (code "73") (name "/USART4_TX") (class "Default")
      (node (ref "*") (pin "2") (pinfunction "2_2") (pintype "passive"))
      (node (ref "U1") (pin "78") (pinfunction "PC10_78") (pintype "passive"))
    )
    (net (code "74") (name "/VALVES_EN") (class "Default")
      (node (ref "U1") (pin "43") (pinfunction "PE12_43") (pintype "passive"))
      (node (ref "U2") (pin "2") (pinfunction "A1_2") (pintype "input"))
    )
    (net (code "75") (name "/VALVES_ENABLE") (class "Default")
      (node (ref "J1") (pin "13") (pinfunction "13_13") (pintype "passive"))
      (node (ref "R2") (pin "2") (pinfunction "2_2") (pintype "passive"))
    )
    (net (code "76") (name "GND_D") (class "Default")
      (node (ref "*") (pin "4") (pinfunction "4_4") (pintype "passive"))
      (node (ref "1") (pin "1") (pinfunction "GND_1") (pintype "passive"))
      (node (ref "2") (pin "4") (pinfunction "4_4") (pintype "passive"))
      (node (ref "C1") (pin "2") (pinfunction "2_2") (pintype "passive"))
      (node (ref "C10") (pin "2") (pinfunction "2_2") (pintype "passive"))
      (node (ref "C11") (pin "2") (pinfunction "2_2") (pintype "passive"))
      (node (ref "C12") (pin "2") (pinfunction "2_2") (pintype "passive"))
      (node (ref "C13") (pin "2") (pinfunction "2_2") (pintype "passive"))
      (node (ref "C14") (pin "2") (pinfunction "2_2") (pintype "passive"))
      (node (ref "C15") (pin "2") (pinfunction "2_2") (pintype "passive"))
      (node (ref "C16") (pin "2") (pinfunction "2_2") (pintype "passive"))
      (node (ref "C17") (pin "2") (pinfunction "K_2") (pintype "passive"))
      (node (ref "C18") (pin "2") (pinfunction "K_2") (pintype "passive"))
      (node (ref "C19") (pin "2") (pinfunction "2_2") (pintype "passive"))
      (node (ref "C2") (pin "2") (pinfunction "2_2") (pintype "passive"))
      (node (ref "C20") (pin "2") (pinfunction "2_2") (pintype "passive"))
      (node (ref "C21") (pin "2") (pinfunction "2_2") (pintype "passive"))
      (node (ref "C22") (pin "2") (pinfunction "2_2") (pintype "passive"))
      (node (ref "C23") (pin "2") (pinfunction "2_2") (pintype "passive"))
      (node (ref "C24") (pin "1") (pinfunction "1_1") (pintype "passive"))
      (node (ref "C3") (pin "1") (pinfunction "1_1") (pintype "passive"))
      (node (ref "C4") (pin "2") (pinfunction "2_2") (pintype "passive"))
      (node (ref "C5") (pin "2") (pinfunction "2_2") (pintype "passive"))
      (node (ref "C6") (pin "1") (pinfunction "1_1") (pintype "passive"))
      (node (ref "C7") (pin "1") (pinfunction "1_1") (pintype "passive"))
      (node (ref "C8") (pin "2") (pinfunction "2_2") (pintype "passive"))
      (node (ref "C9") (pin "1") (pinfunction "1_1") (pintype "passive"))
      (node (ref "D1") (pin "2") (pinfunction "K_2") (pintype "passive"))
      (node (ref "D2") (pin "2") (pinfunction "K_2") (pintype "passive"))
      (node (ref "D3") (pin "2") (pinfunction "K_2") (pintype "passive"))
      (node (ref "GL1") (pin "2") (pinfunction "GND_2") (pintype "passive"))
      (node (ref "J2") (pin "1") (pinfunction "1_1") (pintype "passive"))
      (node (ref "J2") (pin "2") (pinfunction "2_2") (pintype "passive"))
      (node (ref "J3") (pin "1") (pinfunction "1_1") (pintype "passive"))
      (node (ref "J3") (pin "10") (pinfunction "10_10") (pintype "passive"))
      (node (ref "J3") (pin "11") (pinfunction "11_11") (pintype "passive"))
      (node (ref "J3") (pin "12") (pinfunction "12_12") (pintype "passive"))
      (node (ref "J3") (pin "13") (pinfunction "13_13") (pintype "passive"))
      (node (ref "J3") (pin "14") (pinfunction "14_14") (pintype "passive"))
      (node (ref "J3") (pin "15") (pinfunction "15_15") (pintype "passive"))
      (node (ref "J3") (pin "16") (pinfunction "16_16") (pintype "passive"))
      (node (ref "J3") (pin "17") (pinfunction "17_17") (pintype "passive"))
      (node (ref "J3") (pin "18") (pinfunction "18_18") (pintype "passive"))
      (node (ref "J3") (pin "19") (pinfunction "19_19") (pintype "passive"))
      (node (ref "J3") (pin "2") (pinfunction "2_2") (pintype "passive"))
      (node (ref "J3") (pin "20") (pinfunction "20_20") (pintype "passive"))
      (node (ref "J3") (pin "3") (pinfunction "3_3") (pintype "passive"))
      (node (ref "J3") (pin "4") (pinfunction "4_4") (pintype "passive"))
      (node (ref "J3") (pin "5") (pinfunction "5_5") (pintype "passive"))
      (node (ref "J3") (pin "6") (pinfunction "6_6") (pintype "passive"))
      (node (ref "J3") (pin "7") (pinfunction "7_7") (pintype "passive"))
      (node (ref "J3") (pin "8") (pinfunction "8_8") (pintype "passive"))
      (node (ref "J3") (pin "9") (pinfunction "9_9") (pintype "passive"))
      (node (ref "K1") (pin "1") (pinfunction "1_1") (pintype "passive"))
      (node (ref "K2") (pin "1") (pinfunction "1_1") (pintype "passive"))
      (node (ref "K3") (pin "1") (pinfunction "1_1") (pintype "passive"))
      (node (ref "K4") (pin "1") (pinfunction "1_1") (pintype "passive"))
      (node (ref "P1") (pin "5") (pinfunction "Pin_5") (pintype "passive"))
      (node (ref "P1") (pin "6") (pinfunction "Pin_6") (pintype "passive"))
      (node (ref "R1") (pin "2") (pinfunction "2_2") (pintype "passive"))
      (node (ref "R14") (pin "2") (pinfunction "2_2") (pintype "passive"))
      (node (ref "R23") (pin "1") (pinfunction "1_1") (pintype "passive"))
      (node (ref "R26") (pin "1") (pinfunction "1_1") (pintype "passive"))
      (node (ref "R27") (pin "2") (pinfunction "2_2") (pintype "passive"))
      (node (ref "R34") (pin "1") (pinfunction "1_1") (pintype "passive"))
      (node (ref "R35") (pin "2") (pinfunction "2_2") (pintype "passive"))
      (node (ref "U1") (pin "10") (pinfunction "VSS_5_10") (pintype "passive"))
      (node (ref "U1") (pin "19") (pinfunction "VSSA_19") (pintype "passive"))
      (node (ref "U1") (pin "20") (pinfunction "VREF-_20") (pintype "passive"))
      (node (ref "U1") (pin "27") (pinfunction "VSS_4_27") (pintype "passive"))
      (node (ref "U1") (pin "49") (pinfunction "VSS_1_49") (pintype "passive"))
      (node (ref "U1") (pin "74") (pinfunction "VSS_2_74") (pintype "passive"))
      (node (ref "U1") (pin "99") (pinfunction "VSS_3_99") (pintype "passive"))
      (node (ref "U2") (pin "1") (pinfunction "ENA_1") (pintype "input"))
      (node (ref "U2") (pin "10") (pinfunction "GND_10") (pintype "power_in"))
      (node (ref "U2") (pin "11") (pinfunction "B1_11") (pintype "input"))
      (node (ref "U2") (pin "13") (pinfunction "B2_13") (pintype "input"))
      (node (ref "U2") (pin "15") (pinfunction "B3_15") (pintype "input"))
      (node (ref "U2") (pin "17") (pinfunction "B4_17") (pintype "input"))
      (node (ref "U2") (pin "19") (pinfunction "ENB_19") (pintype "input"))
      (node (ref "U2") (pin "8") (pinfunction "A4_8") (pintype "input"))
      (node (ref "U3") (pin "1") (pinfunction "ENA_1") (pintype "input"))
      (node (ref "U3") (pin "10") (pinfunction "GND_10") (pintype "power_in"))
      (node (ref "U3") (pin "19") (pinfunction "ENB_19") (pintype "input"))
      (node (ref "U4") (pin "1") (pinfunction "ENA_1") (pintype "input"))
      (node (ref "U4") (pin "10") (pinfunction "GND_10") (pintype "power_in"))
      (node (ref "U4") (pin "19") (pinfunction "ENB_19") (pintype "input"))
      (node (ref "U5") (pin "7") (pinfunction "GND_7") (pintype "passive"))
      (node (ref "U6") (pin "3") (pinfunction "GND_3") (pintype "passive"))
      (node (ref "U6") (pin "4") (pinfunction "GND_4") (pintype "passive"))
      (node (ref "U6") (pin "5") (pinfunction "GND_5") (pintype "passive"))
      (node (ref "U6") (pin "6") (pinfunction "GND_6") (pintype "passive"))
      (node (ref "U7") (pin "7") (pinfunction "GND_7") (pintype "passive"))
      (node (ref "U8") (pin "1") (pinfunction "GND_1") (pintype "power_in"))
    )
    (net (code "77") (name "Net-(D2-A)") (class "Default")
      (node (ref "D2") (pin "1") (pinfunction "A_1") (pintype "passive"))
      (node (ref "R28") (pin "1") (pinfunction "1_1") (pintype "passive"))
    )
    (net (code "78") (name "Net-(D3-A)") (class "Default")
      (node (ref "D3") (pin "1") (pinfunction "A_1") (pintype "passive"))
      (node (ref "R29") (pin "1") (pinfunction "1_1") (pintype "passive"))
    )
    (net (code "79") (name "Net-(D4-A)") (class "Default")
      (node (ref "D4") (pin "1") (pinfunction "A_1") (pintype "passive"))
      (node (ref "R40") (pin "1") (pinfunction "1_1") (pintype "passive"))
    )
    (net (code "80") (name "Net-(D5-A)") (class "Default")
      (node (ref "D5") (pin "1") (pinfunction "A_1") (pintype "passive"))
      (node (ref "R41") (pin "1") (pinfunction "1_1") (pintype "passive"))
    )
    (net (code "81") (name "Net-(D6-A)") (class "Default")
      (node (ref "D6") (pin "1") (pinfunction "A_1") (pintype "passive"))
      (node (ref "R42") (pin "1") (pinfunction "1_1") (pintype "passive"))
    )
    (net (code "82") (name "Net-(U1-BOOT0)") (class "Default")
      (node (ref "R1") (pin "1") (pinfunction "1_1") (pintype "passive"))
      (node (ref "U1") (pin "94") (pinfunction "BOOT0_94") (pintype "passive"))
    )
    (net (code "83") (name "Net-(U1-OSC_IN)") (class "Default")
      (node (ref "C7") (pin "2") (pinfunction "2_2") (pintype "passive"))
      (node (ref "U1") (pin "12") (pinfunction "OSC_IN_12") (pintype "passive"))
      (node (ref "Y2") (pin "2") (pinfunction "OSC2_2") (pintype "passive"))
    )
    (net (code "84") (name "Net-(U1-OSC_OUT)") (class "Default")
      (node (ref "C8") (pin "1") (pinfunction "1_1") (pintype "passive"))
      (node (ref "U1") (pin "13") (pinfunction "OSC_OUT_13") (pintype "passive"))
      (node (ref "Y2") (pin "1") (pinfunction "OSC1_1") (pintype "passive"))
    )
    (net (code "85") (name "Net-(U1-PB2{slash}BOOT1)") (class "Default")
      (node (ref "R14") (pin "1") (pinfunction "1_1") (pintype "passive"))
      (node (ref "U1") (pin "37") (pinfunction "PB2/BOOT1_37") (pintype "passive"))
    )
    (net (code "86") (name "Net-(U1-PC14-OSC32-IN)") (class "Default")
      (node (ref "C4") (pin "1") (pinfunction "1_1") (pintype "passive"))
      (node (ref "U1") (pin "8") (pinfunction "PC14-OSC32-IN_8") (pintype "passive"))
      (node (ref "Y1") (pin "2") (pinfunction "OSC2_2") (pintype "passive"))
    )
    (net (code "87") (name "Net-(U1-PC15-OSC32-OUT)") (class "Default")
      (node (ref "C5") (pin "1") (pinfunction "1_1") (pintype "passive"))
      (node (ref "U1") (pin "9") (pinfunction "PC15-OSC32-OUT_9") (pintype "passive"))
      (node (ref "Y1") (pin "1") (pinfunction "OSC1_1") (pintype "passive"))
    )
    (net (code "88") (name "Net-(U1-VDD_4)") (class "Default")
      (node (ref "C12") (pin "1") (pinfunction "1_1") (pintype "passive"))
      (node (ref "U1") (pin "28") (pinfunction "VDD_4_28") (pintype "passive"))
    )
    (net (code "89") (name "Net-(U2-YA1)") (class "Default")
      (node (ref "R2") (pin "1") (pinfunction "1_1") (pintype "passive"))
      (node (ref "U2") (pin "18") (pinfunction "YA1_18") (pintype "output"))
    )
    (net (code "90") (name "Net-(U2-YA2)") (class "Default")
      (node (ref "R3") (pin "1") (pinfunction "1_1") (pintype "passive"))
      (node (ref "U2") (pin "16") (pinfunction "YA2_16") (pintype "output"))
    )
    (net (code "91") (name "Net-(U2-YA3)") (class "Default")
      (node (ref "R4") (pin "1") (pinfunction "1_1") (pintype "passive"))
      (node (ref "U2") (pin "14") (pinfunction "YA3_14") (pintype "output"))
    )
    (net (code "92") (name "Net-(U3-YA1)") (class "Default")
      (node (ref "R5") (pin "1") (pinfunction "1_1") (pintype "passive"))
      (node (ref "U3") (pin "18") (pinfunction "YA1_18") (pintype "output"))
    )
    (net (code "93") (name "Net-(U3-YA2)") (class "Default")
      (node (ref "R6") (pin "1") (pinfunction "1_1") (pintype "passive"))
      (node (ref "U3") (pin "16") (pinfunction "YA2_16") (pintype "output"))
    )
    (net (code "94") (name "Net-(U3-YA3)") (class "Default")
      (node (ref "R7") (pin "1") (pinfunction "1_1") (pintype "passive"))
      (node (ref "U3") (pin "14") (pinfunction "YA3_14") (pintype "output"))
    )
    (net (code "95") (name "Net-(U3-YA4)") (class "Default")
      (node (ref "R8") (pin "1") (pinfunction "1_1") (pintype "passive"))
      (node (ref "U3") (pin "12") (pinfunction "YA4_12") (pintype "output"))
    )
    (net (code "96") (name "Net-(U3-YB1)") (class "Default")
      (node (ref "R9") (pin "1") (pinfunction "1_1") (pintype "passive"))
      (node (ref "U3") (pin "9") (pinfunction "YB1_9") (pintype "output"))
    )
    (net (code "97") (name "Net-(U3-YB2)") (class "Default")
      (node (ref "R11") (pin "1") (pinfunction "1_1") (pintype "passive"))
      (node (ref "U3") (pin "7") (pinfunction "YB2_7") (pintype "output"))
    )
    (net (code "98") (name "Net-(U3-YB3)") (class "Default")
      (node (ref "R12") (pin "1") (pinfunction "1_1") (pintype "passive"))
      (node (ref "U3") (pin "5") (pinfunction "YB3_5") (pintype "output"))
    )
    (net (code "99") (name "Net-(U3-YB4)") (class "Default")
      (node (ref "R13") (pin "1") (pinfunction "1_1") (pintype "passive"))
      (node (ref "U3") (pin "3") (pinfunction "YB4_3") (pintype "output"))
    )
    (net (code "100") (name "Net-(U4-YA1)") (class "Default")
      (node (ref "R15") (pin "1") (pinfunction "1_1") (pintype "passive"))
      (node (ref "U4") (pin "18") (pinfunction "YA1_18") (pintype "output"))
    )
    (net (code "101") (name "Net-(U4-YA2)") (class "Default")
      (node (ref "R16") (pin "1") (pinfunction "1_1") (pintype "passive"))
      (node (ref "U4") (pin "16") (pinfunction "YA2_16") (pintype "output"))
    )
    (net (code "102") (name "Net-(U4-YA3)") (class "Default")
      (node (ref "R17") (pin "1") (pinfunction "1_1") (pintype "passive"))
      (node (ref "U4") (pin "14") (pinfunction "YA3_14") (pintype "output"))
    )
    (net (code "103") (name "Net-(U4-YB1)") (class "Default")
      (node (ref "R19") (pin "1") (pinfunction "1_1") (pintype "passive"))
      (node (ref "U4") (pin "9") (pinfunction "YB1_9") (pintype "output"))
    )
    (net (code "104") (name "Net-(U4-YB2)") (class "Default")
      (node (ref "R20") (pin "1") (pinfunction "1_1") (pintype "passive"))
      (node (ref "U4") (pin "7") (pinfunction "YB2_7") (pintype "output"))
    )
    (net (code "105") (name "Net-(U4-YB3)") (class "Default")
      (node (ref "R21") (pin "1") (pinfunction "1_1") (pintype "passive"))
      (node (ref "U4") (pin "5") (pinfunction "YB3_5") (pintype "output"))
    )
    (net (code "106") (name "Net-(U4-YB4)") (class "Default")
      (node (ref "R18") (pin "1") (pinfunction "1_1") (pintype "passive"))
      (node (ref "U4") (pin "3") (pinfunction "YB4_3") (pintype "output"))
    )
    (net (code "107") (name "Net-(U5-1Y)") (class "Default")
      (node (ref "R24") (pin "1") (pinfunction "1_1") (pintype "passive"))
      (node (ref "U5") (pin "6") (pinfunction "1Y_6") (pintype "passive"))
    )
    (net (code "108") (name "Net-(U5-2Y)") (class "Default")
      (node (ref "R25") (pin "1") (pinfunction "1_1") (pintype "passive"))
      (node (ref "U5") (pin "8") (pinfunction "2Y_8") (pintype "passive"))
    )
    (net (code "109") (name "Net-(U7-1D)") (class "Default")
      (node (ref "R30") (pin "1") (pinfunction "1_1") (pintype "passive"))
      (node (ref "U7") (pin "5") (pinfunction "1D_5") (pintype "passive"))
    )
    (net (code "110") (name "Net-(U7-1Y)") (class "Default")
      (node (ref "R31") (pin "1") (pinfunction "1_1") (pintype "passive"))
      (node (ref "U7") (pin "6") (pinfunction "1Y_6") (pintype "passive"))
    )
    (net (code "111") (name "Net-(U7-2A)") (class "Default")
      (node (ref "R32") (pin "2") (pinfunction "2_2") (pintype "passive"))
      (node (ref "U7") (pin "9") (pinfunction "2A_9") (pintype "passive"))
    )
    (net (code "112") (name "Net-(U7-2Y)") (class "Default")
      (node (ref "R33") (pin "2") (pinfunction "2_2") (pintype "passive"))
      (node (ref "U7") (pin "8") (pinfunction "2Y_8") (pintype "passive"))
    )
    (net (code "113") (name "VCC_3V3") (class "Default")
      (node (ref "1") (pin "2") (pinfunction "VCC_2") (pintype "passive"))
      (node (ref "2") (pin "1") (pinfunction "1_1") (pintype "passive"))
      (node (ref "C1") (pin "1") (pinfunction "1_1") (pintype "passive"))
      (node (ref "C13") (pin "1") (pinfunction "1_1") (pintype "passive"))
      (node (ref "C18") (pin "1") (pinfunction "A_1") (pintype "passive"))
      (node (ref "C20") (pin "1") (pinfunction "1_1") (pintype "passive"))
      (node (ref "C3") (pin "2") (pinfunction "2_2") (pintype "passive"))
      (node (ref "C6") (pin "2") (pinfunction "2_2") (pintype "passive"))
      (node (ref "L1") (pin "1") (pinfunction "1_1") (pintype "passive"))
      (node (ref "R10") (pin "1") (pinfunction "1_1") (pintype "passive"))
      (node (ref "R22") (pin "2") (pinfunction "2_2") (pintype "passive"))
      (node (ref "R37") (pin "2") (pinfunction "2_2") (pintype "passive"))
      (node (ref "R38") (pin "2") (pinfunction "2_2") (pintype "passive"))
      (node (ref "R39") (pin "2") (pinfunction "2_2") (pintype "passive"))
      (node (ref "R40") (pin "2") (pinfunction "2_2") (pintype "passive"))
      (node (ref "R41") (pin "2") (pinfunction "2_2") (pintype "passive"))
      (node (ref "R42") (pin "2") (pinfunction "2_2") (pintype "passive"))
      (node (ref "U1") (pin "100") (pinfunction "VDD_3_100") (pintype "passive"))
      (node (ref "U1") (pin "11") (pinfunction "VDD_5_11") (pintype "passive"))
      (node (ref "U1") (pin "50") (pinfunction "VDD_1_50") (pintype "passive"))
      (node (ref "U1") (pin "75") (pinfunction "VDD_2_75") (pintype "passive"))
      (node (ref "U8") (pin "2") (pinfunction "OUT_2") (pintype "power_in"))
    )
    (net (code "114") (name "VCC_5V") (class "Default")
      (node (ref "*") (pin "5") (pinfunction "5_5") (pintype "passive"))
      (node (ref "C14") (pin "1") (pinfunction "1_1") (pintype "passive"))
      (node (ref "C15") (pin "1") (pinfunction "1_1") (pintype "passive"))
      (node (ref "C16") (pin "1") (pinfunction "1_1") (pintype "passive"))
      (node (ref "C17") (pin "1") (pinfunction "A_1") (pintype "passive"))
      (node (ref "C19") (pin "1") (pinfunction "1_1") (pintype "passive"))
      (node (ref "C2") (pin "1") (pinfunction "1_1") (pintype "passive"))
      (node (ref "C24") (pin "2") (pinfunction "2_2") (pintype "passive"))
      (node (ref "C9") (pin "2") (pinfunction "2_2") (pintype "passive"))
      (node (ref "GL1") (pin "1") (pinfunction "VIN_1") (pintype "passive"))
      (node (ref "P1") (pin "11") (pinfunction "Pin_11") (pintype "passive"))
      (node (ref "P1") (pin "12") (pinfunction "Pin_12") (pintype "passive"))
      (node (ref "R28") (pin "2") (pinfunction "2_2") (pintype "passive"))
      (node (ref "R30") (pin "2") (pinfunction "2_2") (pintype "passive"))
      (node (ref "R32") (pin "1") (pinfunction "1_1") (pintype "passive"))
      (node (ref "U2") (pin "20") (pinfunction "VCC_20") (pintype "power_in"))
      (node (ref "U3") (pin "20") (pinfunction "VCC_20") (pintype "power_in"))
      (node (ref "U4") (pin "20") (pinfunction "VCC_20") (pintype "power_in"))
      (node (ref "U5") (pin "14") (pinfunction "VCC_14") (pintype "passive"))
      (node (ref "U6") (pin "1") (pinfunction "VOUT+_1") (pintype "passive"))
      (node (ref "U6") (pin "2") (pinfunction "VOUT+_2") (pintype "passive"))
      (node (ref "U7") (pin "14") (pinfunction "VCC_14") (pintype "passive"))
      (node (ref "U8") (pin "3") (pinfunction "IN_3") (pintype "power_in"))
    )
    (net (code "115") (name "VCC_14V") (class "Default")
      (node (ref "D1") (pin "1") (pinfunction "A_1") (pintype "passive"))
      (node (ref "J2") (pin "3") (pinfunction "3_3") (pintype "passive"))
      (node (ref "J2") (pin "4") (pinfunction "4_4") (pintype "passive"))
      (node (ref "R29") (pin "2") (pinfunction "2_2") (pintype "passive"))
      (node (ref "U6") (pin "7") (pinfunction "VIN+_7") (pintype "passive"))
      (node (ref "U6") (pin "8") (pinfunction "VIN+_8") (pintype "passive"))
    )
    (net (code "116") (name "unconnected-(*-Pad1)") (class "Default")
      (node (ref "*") (pin "1") (pinfunction "1_1") (pintype "passive+no_connect"))
    )
    (net (code "117") (name "unconnected-(*-Pad6)") (class "Default")
      (node (ref "*") (pin "6") (pinfunction "6_6") (pintype "passive+no_connect"))
    )
    (net (code "118") (name "unconnected-(GL1-CANG-Pad8)") (class "Default")
      (node (ref "GL1") (pin "8") (pinfunction "CANG_8") (pintype "passive+no_connect"))
    )
    (net (code "119") (name "unconnected-(J1-Pad1)") (class "Default")
      (node (ref "J1") (pin "1") (pinfunction "1_1") (pintype "passive"))
    )
    (net (code "120") (name "unconnected-(J1-Pad2)") (class "Default")
      (node (ref "J1") (pin "2") (pinfunction "2_2") (pintype "passive"))
    )
    (net (code "121") (name "unconnected-(J2-Pad5)") (class "Default")
      (node (ref "J2") (pin "5") (pinfunction "5_5") (pintype "passive"))
    )
    (net (code "122") (name "unconnected-(J2-Pad6)") (class "Default")
      (node (ref "J2") (pin "6") (pinfunction "6_6") (pintype "passive"))
    )
    (net (code "123") (name "unconnected-(P1-Pin-Pad3)") (class "Default")
      (node (ref "P1") (pin "3") (pinfunction "Pin_3") (pintype "passive"))
    )
    (net (code "124") (name "unconnected-(P1-Pin-Pad4)") (class "Default")
      (node (ref "P1") (pin "4") (pinfunction "Pin_4") (pintype "passive"))
    )
    (net (code "125") (name "unconnected-(P1-Pin-Pad9)") (class "Default")
      (node (ref "P1") (pin "9") (pinfunction "Pin_9") (pintype "passive"))
    )
    (net (code "126") (name "unconnected-(P1-Pin-Pad10)") (class "Default")
      (node (ref "P1") (pin "10") (pinfunction "Pin_10") (pintype "passive"))
    )
    (net (code "127") (name "unconnected-(U1-NC-Pad73)") (class "Default")
      (node (ref "U1") (pin "73") (pinfunction "NC_73") (pintype "passive"))
    )
    (net (code "128") (name "unconnected-(U1-PA3-Pad26)") (class "Default")
      (node (ref "U1") (pin "26") (pinfunction "PA3_26") (pintype "passive"))
    )
    (net (code "129") (name "unconnected-(U1-PA4-Pad29)") (class "Default")
      (node (ref "U1") (pin "29") (pinfunction "PA4_29") (pintype "passive"))
    )
    (net (code "130") (name "unconnected-(U1-PA5-Pad30)") (class "Default")
      (node (ref "U1") (pin "30") (pinfunction "PA5_30") (pintype "passive"))
    )
    (net (code "131") (name "unconnected-(U1-PA8-Pad67)") (class "Default")
      (node (ref "U1") (pin "67") (pinfunction "PA8_67") (pintype "passive"))
    )
    (net (code "132") (name "unconnected-(U1-PA9-Pad68)") (class "Default")
      (node (ref "U1") (pin "68") (pinfunction "PA9_68") (pintype "passive"))
    )
    (net (code "133") (name "unconnected-(U1-PA10-Pad69)") (class "Default")
      (node (ref "U1") (pin "69") (pinfunction "PA10_69") (pintype "passive"))
    )
    (net (code "134") (name "unconnected-(U1-PA15-Pad77)") (class "Default")
      (node (ref "U1") (pin "77") (pinfunction "PA15_77") (pintype "passive"))
    )
    (net (code "135") (name "unconnected-(U1-PB4-Pad90)") (class "Default")
      (node (ref "U1") (pin "90") (pinfunction "PB4_90") (pintype "passive"))
    )
    (net (code "136") (name "unconnected-(U1-PB5-Pad91)") (class "Default")
      (node (ref "U1") (pin "91") (pinfunction "PB5_91") (pintype "passive"))
    )
    (net (code "137") (name "unconnected-(U1-PB10-Pad47)") (class "Default")
      (node (ref "U1") (pin "47") (pinfunction "PB10_47") (pintype "passive"))
    )
    (net (code "138") (name "unconnected-(U1-PB11-Pad48)") (class "Default")
      (node (ref "U1") (pin "48") (pinfunction "PB11_48") (pintype "passive"))
    )
    (net (code "139") (name "unconnected-(U1-PB13-Pad52)") (class "Default")
      (node (ref "U1") (pin "52") (pinfunction "PB13_52") (pintype "passive"))
    )
    (net (code "140") (name "unconnected-(U1-PB15-Pad54)") (class "Default")
      (node (ref "U1") (pin "54") (pinfunction "PB15_54") (pintype "passive"))
    )
    (net (code "141") (name "unconnected-(U1-PC0-Pad15)") (class "Default")
      (node (ref "U1") (pin "15") (pinfunction "PC0_15") (pintype "passive"))
    )
    (net (code "142") (name "unconnected-(U1-PC1-Pad16)") (class "Default")
      (node (ref "U1") (pin "16") (pinfunction "PC1_16") (pintype "passive"))
    )
    (net (code "143") (name "unconnected-(U1-PC2-Pad17)") (class "Default")
      (node (ref "U1") (pin "17") (pinfunction "PC2_17") (pintype "passive"))
    )
    (net (code "144") (name "unconnected-(U1-PC3-Pad18)") (class "Default")
      (node (ref "U1") (pin "18") (pinfunction "PC3_18") (pintype "passive"))
    )
    (net (code "145") (name "unconnected-(U1-PC4-Pad33)") (class "Default")
      (node (ref "U1") (pin "33") (pinfunction "PC4_33") (pintype "passive"))
    )
    (net (code "146") (name "unconnected-(U1-PC5-Pad34)") (class "Default")
      (node (ref "U1") (pin "34") (pinfunction "PC5_34") (pintype "passive"))
    )
    (net (code "147") (name "unconnected-(U1-PC12-Pad80)") (class "Default")
      (node (ref "U1") (pin "80") (pinfunction "PC12_80") (pintype "passive"))
    )
    (net (code "148") (name "unconnected-(U1-PC13-ANTI_TAMP-Pad7)") (class "Default")
      (node (ref "U1") (pin "7") (pinfunction "PC13-ANTI_TAMP_7") (pintype "passive"))
    )
    (net (code "149") (name "unconnected-(U1-PD1-Pad82)") (class "Default")
      (node (ref "U1") (pin "82") (pinfunction "PD1_82") (pintype "passive"))
    )
    (net (code "150") (name "unconnected-(U1-PD2-Pad83)") (class "Default")
      (node (ref "U1") (pin "83") (pinfunction "PD2_83") (pintype "passive"))
    )
    (net (code "151") (name "unconnected-(U1-PD4-Pad85)") (class "Default")
      (node (ref "U1") (pin "85") (pinfunction "PD4_85") (pintype "passive"))
    )
    (net (code "152") (name "unconnected-(U1-PD6-Pad87)") (class "Default")
      (node (ref "U1") (pin "87") (pinfunction "PD6_87") (pintype "passive"))
    )
    (net (code "153") (name "unconnected-(U1-PD7-Pad88)") (class "Default")
      (node (ref "U1") (pin "88") (pinfunction "PD7_88") (pintype "passive"))
    )
    (net (code "154") (name "unconnected-(U1-PD8-Pad55)") (class "Default")
      (node (ref "U1") (pin "55") (pinfunction "PD8_55") (pintype "passive"))
    )
    (net (code "155") (name "unconnected-(U1-PD10-Pad57)") (class "Default")
      (node (ref "U1") (pin "57") (pinfunction "PD10_57") (pintype "passive"))
    )
    (net (code "156") (name "unconnected-(U1-PE0-Pad97)") (class "Default")
      (node (ref "U1") (pin "97") (pinfunction "PE0_97") (pintype "passive"))
    )
    (net (code "157") (name "unconnected-(U1-PE1-Pad98)") (class "Default")
      (node (ref "U1") (pin "98") (pinfunction "PE1_98") (pintype "passive"))
    )
    (net (code "158") (name "unconnected-(U1-PE5-Pad4)") (class "Default")
      (node (ref "U1") (pin "4") (pinfunction "PE5_4") (pintype "passive"))
    )
    (net (code "159") (name "unconnected-(U1-PE6-Pad5)") (class "Default")
      (node (ref "U1") (pin "5") (pinfunction "PE6_5") (pintype "passive"))
    )
    (net (code "160") (name "unconnected-(U1-PE7-Pad38)") (class "Default")
      (node (ref "U1") (pin "38") (pinfunction "PE7_38") (pintype "passive"))
    )
    (net (code "161") (name "unconnected-(U1-PE8-Pad39)") (class "Default")
      (node (ref "U1") (pin "39") (pinfunction "PE8_39") (pintype "passive"))
    )
    (net (code "162") (name "unconnected-(U1-PE9-Pad40)") (class "Default")
      (node (ref "U1") (pin "40") (pinfunction "PE9_40") (pintype "passive"))
    )
    (net (code "163") (name "unconnected-(U1-PE10-Pad41)") (class "Default")
      (node (ref "U1") (pin "41") (pinfunction "PE10_41") (pintype "passive"))
    )
    (net (code "164") (name "unconnected-(U1-PE11-Pad42)") (class "Default")
      (node (ref "U1") (pin "42") (pinfunction "PE11_42") (pintype "passive"))
    )
    (net (code "165") (name "unconnected-(U1-PE15-Pad46)") (class "Default")
      (node (ref "U1") (pin "46") (pinfunction "PE15_46") (pintype "passive"))
    )
    (net (code "166") (name "unconnected-(U1-VBAT-Pad6)") (class "Default")
      (node (ref "U1") (pin "6") (pinfunction "VBAT_6") (pintype "passive"))
    )
    (net (code "167") (name "unconnected-(U2-YA4-Pad12)") (class "Default")
      (node (ref "U2") (pin "12") (pinfunction "YA4_12") (pintype "output+no_connect"))
    )
    (net (code "168") (name "unconnected-(U2-YB1-Pad9)") (class "Default")
      (node (ref "U2") (pin "9") (pinfunction "YB1_9") (pintype "output+no_connect"))
    )
    (net (code "169") (name "unconnected-(U2-YB2-Pad7)") (class "Default")
      (node (ref "U2") (pin "7") (pinfunction "YB2_7") (pintype "output+no_connect"))
    )
    (net (code "170") (name "unconnected-(U2-YB3-Pad5)") (class "Default")
      (node (ref "U2") (pin "5") (pinfunction "YB3_5") (pintype "output+no_connect"))
    )
    (net (code "171") (name "unconnected-(U2-YB4-Pad3)") (class "Default")
      (node (ref "U2") (pin "3") (pinfunction "YB4_3") (pintype "output+no_connect"))
    )
    (net (code "172") (name "unconnected-(U4-A4-Pad8)") (class "Default")
      (node (ref "U4") (pin "8") (pinfunction "A4_8") (pintype "input"))
    )
    (net (code "173") (name "unconnected-(U4-YA4-Pad12)") (class "Default")
      (node (ref "U4") (pin "12") (pinfunction "YA4_12") (pintype "output"))
    )
    (net (code "174") (name "unconnected-(U5-NC-Pad3)") (class "Default")
      (node (ref "U5") (pin "3") (pinfunction "NC_3") (pintype "passive"))
    )
    (net (code "175") (name "unconnected-(U5-NC-Pad11)") (class "Default")
      (node (ref "U5") (pin "11") (pinfunction "NC_11") (pintype "passive"))
    )
    (net (code "176") (name "unconnected-(U7-NC-Pad3)") (class "Default")
      (node (ref "U7") (pin "3") (pinfunction "NC_3") (pintype "passive"))
    )
    (net (code "177") (name "unconnected-(U7-NC-Pad11)") (class "Default")
      (node (ref "U7") (pin "11") (pinfunction "NC_11") (pintype "passive"))
    )
  )
)
